# 2_waffling60-BAK_matrix.net
KiCad netlist of a schematic drawn in Altium Designer
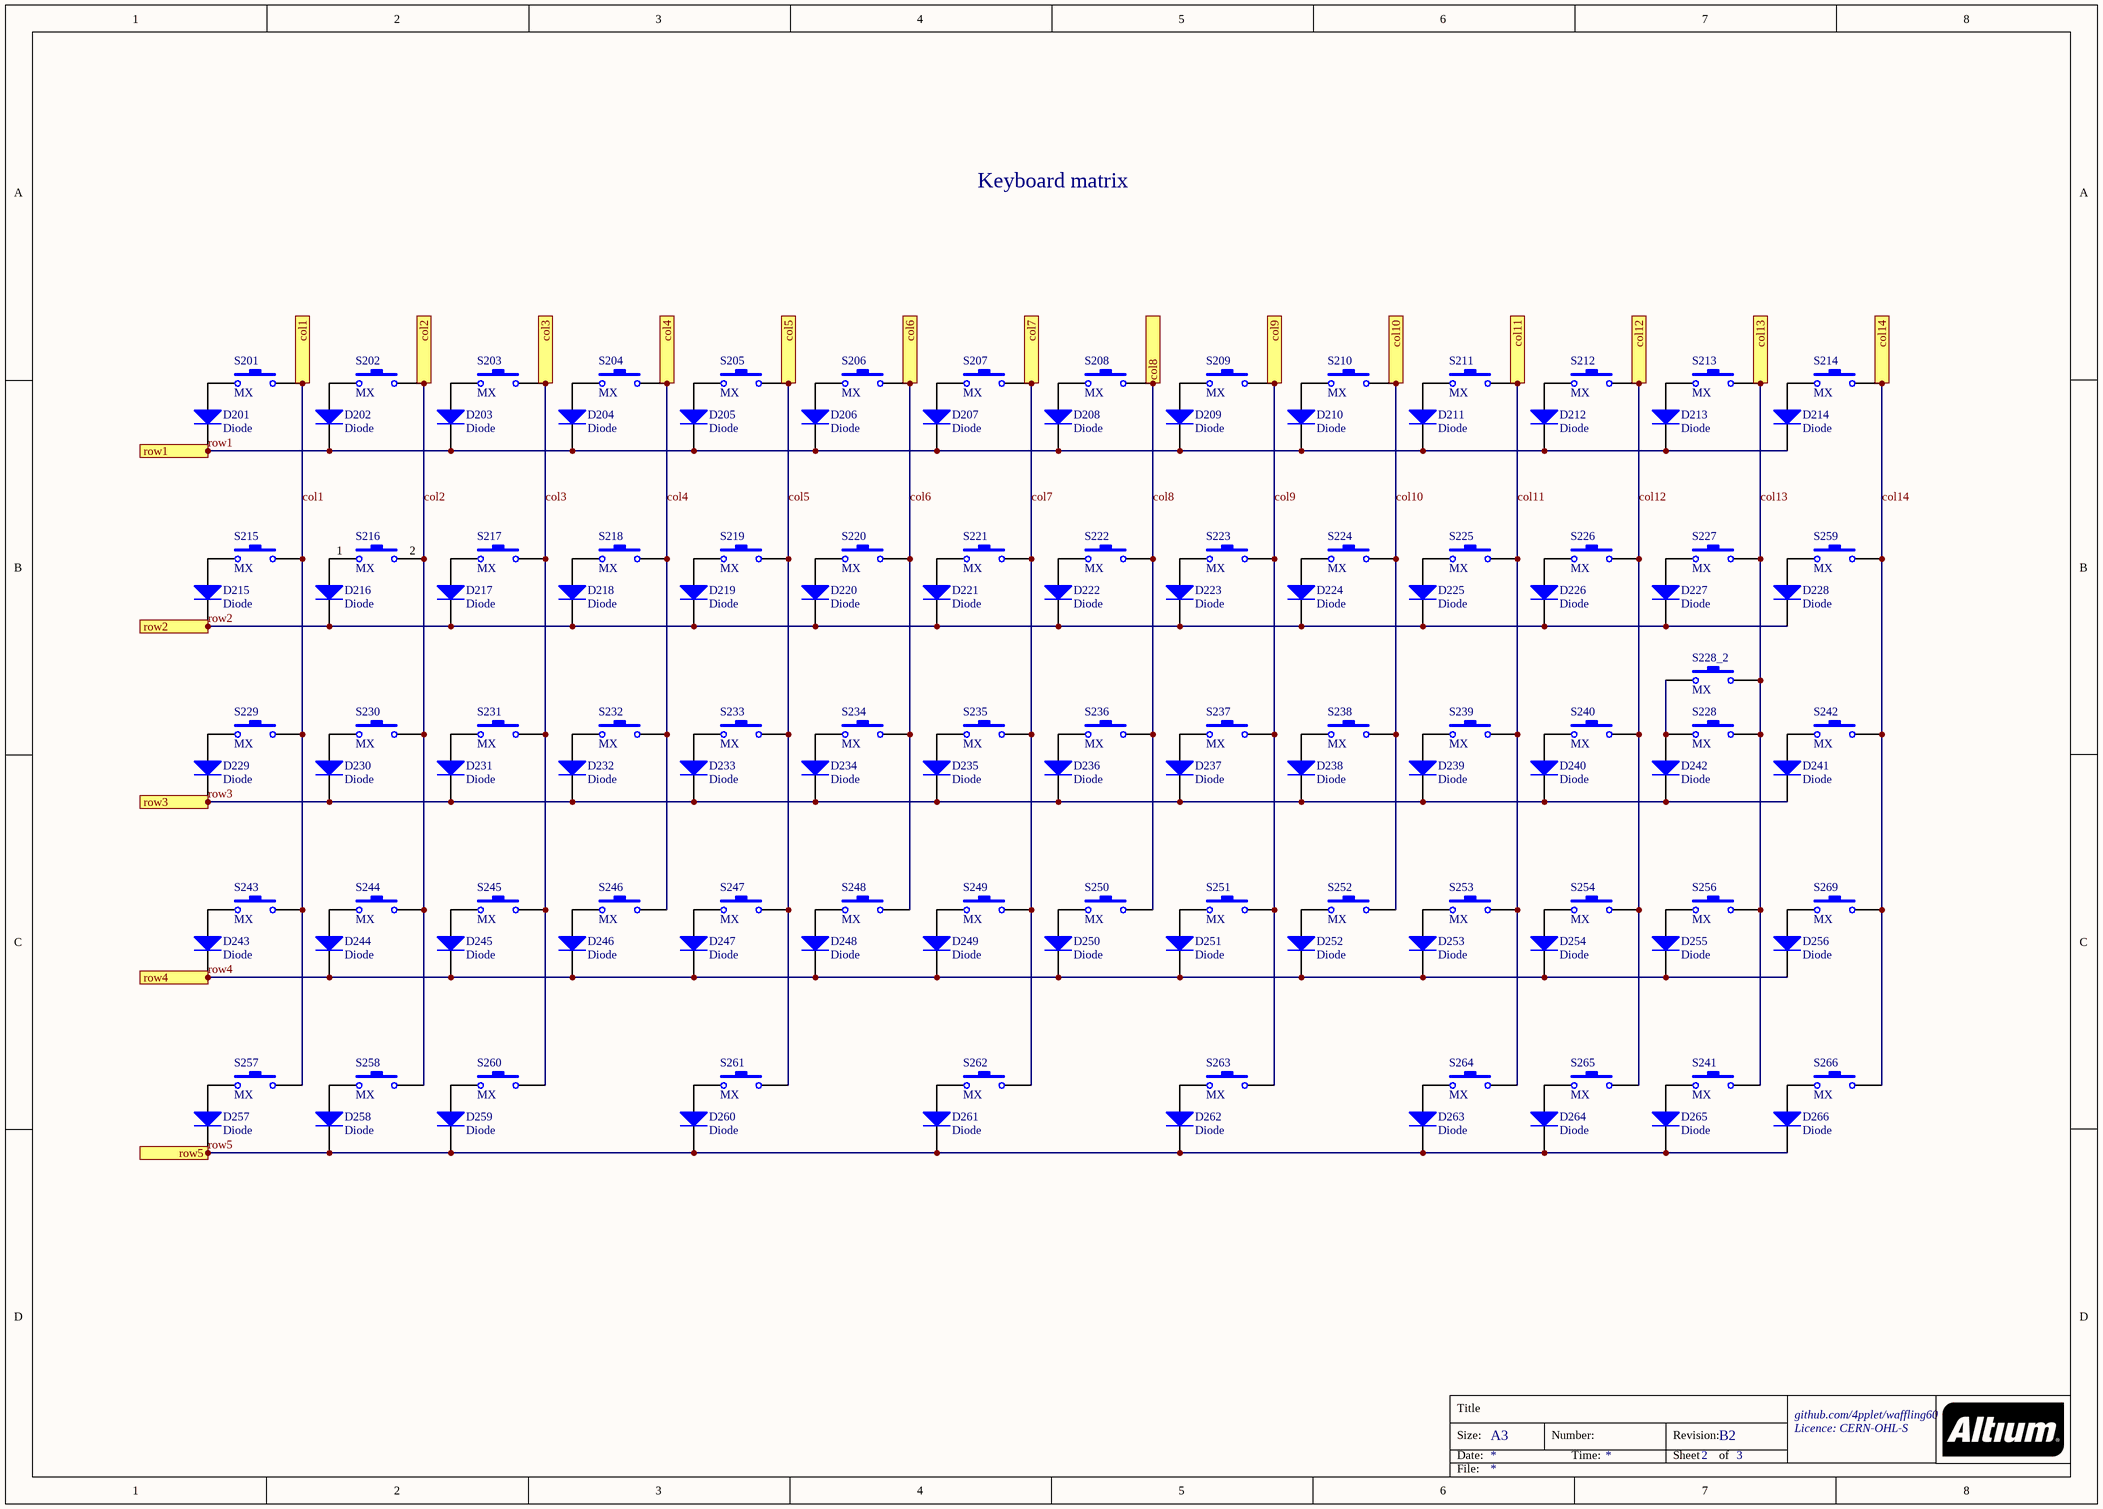
[diagram p0: 2_waffling60-BAK_matrix.SchDoc]

(export (version "E")
  (design (tool "Eeschema 10.0.6"))
  (components
    (comp (ref "D201")
      (value "Diode")
      (footprint "SOD-123")
      (description "Default Diode")
      (fields (field (name "LCSC PART #") "C81598") (field (name "MRF.PART") "1N4148W"))
      (libsource (lib "Miscellaneous Devices") (part "Diode"))
    )
    (comp (ref "D202")
      (value "Diode")
      (footprint "SOD-123")
      (description "Default Diode")
      (fields (field (name "LCSC PART #") "C81598") (field (name "MRF.PART") "1N4148W"))
      (libsource (lib "Miscellaneous Devices") (part "Diode"))
    )
    (comp (ref "D203")
      (value "Diode")
      (footprint "SOD-123")
      (description "Default Diode")
      (fields (field (name "LCSC PART #") "C81598") (field (name "MRF.PART") "1N4148W"))
      (libsource (lib "Miscellaneous Devices") (part "Diode"))
    )
    (comp (ref "D204")
      (value "Diode")
      (footprint "SOD-123")
      (description "Default Diode")
      (fields (field (name "LCSC PART #") "C81598") (field (name "MRF.PART") "1N4148W"))
      (libsource (lib "Miscellaneous Devices") (part "Diode"))
    )
    (comp (ref "D205")
      (value "Diode")
      (footprint "SOD-123")
      (description "Default Diode")
      (fields (field (name "LCSC PART #") "C81598") (field (name "MRF.PART") "1N4148W"))
      (libsource (lib "Miscellaneous Devices") (part "Diode"))
    )
    (comp (ref "D206")
      (value "Diode")
      (footprint "SOD-123")
      (description "Default Diode")
      (fields (field (name "LCSC PART #") "C81598") (field (name "MRF.PART") "1N4148W"))
      (libsource (lib "Miscellaneous Devices") (part "Diode"))
    )
    (comp (ref "D207")
      (value "Diode")
      (footprint "SOD-123")
      (description "Default Diode")
      (fields (field (name "LCSC PART #") "C81598") (field (name "MRF.PART") "1N4148W"))
      (libsource (lib "Miscellaneous Devices") (part "Diode"))
    )
    (comp (ref "D208")
      (value "Diode")
      (footprint "SOD-123")
      (description "Default Diode")
      (fields (field (name "LCSC PART #") "C81598") (field (name "MRF.PART") "1N4148W"))
      (libsource (lib "Miscellaneous Devices") (part "Diode"))
    )
    (comp (ref "D209")
      (value "Diode")
      (footprint "SOD-123")
      (description "Default Diode")
      (fields (field (name "LCSC PART #") "C81598") (field (name "MRF.PART") "1N4148W"))
      (libsource (lib "Miscellaneous Devices") (part "Diode"))
    )
    (comp (ref "D210")
      (value "Diode")
      (footprint "SOD-123")
      (description "Default Diode")
      (fields (field (name "LCSC PART #") "C81598") (field (name "MRF.PART") "1N4148W"))
      (libsource (lib "Miscellaneous Devices") (part "Diode"))
    )
    (comp (ref "D211")
      (value "Diode")
      (footprint "SOD-123")
      (description "Default Diode")
      (fields (field (name "LCSC PART #") "C81598") (field (name "MRF.PART") "1N4148W"))
      (libsource (lib "Miscellaneous Devices") (part "Diode"))
    )
    (comp (ref "D212")
      (value "Diode")
      (footprint "SOD-123")
      (description "Default Diode")
      (fields (field (name "LCSC PART #") "C81598") (field (name "MRF.PART") "1N4148W"))
      (libsource (lib "Miscellaneous Devices") (part "Diode"))
    )
    (comp (ref "D213")
      (value "Diode")
      (footprint "SOD-123")
      (description "Default Diode")
      (fields (field (name "LCSC PART #") "C81598") (field (name "MRF.PART") "1N4148W"))
      (libsource (lib "Miscellaneous Devices") (part "Diode"))
    )
    (comp (ref "D214")
      (value "Diode")
      (footprint "SOD-123")
      (description "Default Diode")
      (fields (field (name "LCSC PART #") "C81598") (field (name "MRF.PART") "1N4148W"))
      (libsource (lib "Miscellaneous Devices") (part "Diode"))
    )
    (comp (ref "D215")
      (value "Diode")
      (footprint "SOD-123")
      (description "Default Diode")
      (fields (field (name "LCSC PART #") "C81598") (field (name "MRF.PART") "1N4148W"))
      (libsource (lib "Miscellaneous Devices") (part "Diode"))
    )
    (comp (ref "D216")
      (value "Diode")
      (footprint "SOD-123")
      (description "Default Diode")
      (fields (field (name "LCSC PART #") "C81598") (field (name "MRF.PART") "1N4148W"))
      (libsource (lib "Miscellaneous Devices") (part "Diode"))
    )
    (comp (ref "D217")
      (value "Diode")
      (footprint "SOD-123")
      (description "Default Diode")
      (fields (field (name "LCSC PART #") "C81598") (field (name "MRF.PART") "1N4148W"))
      (libsource (lib "Miscellaneous Devices") (part "Diode"))
    )
    (comp (ref "D218")
      (value "Diode")
      (footprint "SOD-123")
      (description "Default Diode")
      (fields (field (name "LCSC PART #") "C81598") (field (name "MRF.PART") "1N4148W"))
      (libsource (lib "Miscellaneous Devices") (part "Diode"))
    )
    (comp (ref "D219")
      (value "Diode")
      (footprint "SOD-123")
      (description "Default Diode")
      (fields (field (name "LCSC PART #") "C81598") (field (name "MRF.PART") "1N4148W"))
      (libsource (lib "Miscellaneous Devices") (part "Diode"))
    )
    (comp (ref "D220")
      (value "Diode")
      (footprint "SOD-123")
      (description "Default Diode")
      (fields (field (name "LCSC PART #") "C81598") (field (name "MRF.PART") "1N4148W"))
      (libsource (lib "Miscellaneous Devices") (part "Diode"))
    )
    (comp (ref "D221")
      (value "Diode")
      (footprint "SOD-123")
      (description "Default Diode")
      (fields (field (name "LCSC PART #") "C81598") (field (name "MRF.PART") "1N4148W"))
      (libsource (lib "Miscellaneous Devices") (part "Diode"))
    )
    (comp (ref "D222")
      (value "Diode")
      (footprint "SOD-123")
      (description "Default Diode")
      (fields (field (name "LCSC PART #") "C81598") (field (name "MRF.PART") "1N4148W"))
      (libsource (lib "Miscellaneous Devices") (part "Diode"))
    )
    (comp (ref "D223")
      (value "Diode")
      (footprint "SOD-123")
      (description "Default Diode")
      (fields (field (name "LCSC PART #") "C81598") (field (name "MRF.PART") "1N4148W"))
      (libsource (lib "Miscellaneous Devices") (part "Diode"))
    )
    (comp (ref "D224")
      (value "Diode")
      (footprint "SOD-123")
      (description "Default Diode")
      (fields (field (name "LCSC PART #") "C81598") (field (name "MRF.PART") "1N4148W"))
      (libsource (lib "Miscellaneous Devices") (part "Diode"))
    )
    (comp (ref "D225")
      (value "Diode")
      (footprint "SOD-123")
      (description "Default Diode")
      (fields (field (name "LCSC PART #") "C81598") (field (name "MRF.PART") "1N4148W"))
      (libsource (lib "Miscellaneous Devices") (part "Diode"))
    )
    (comp (ref "D226")
      (value "Diode")
      (footprint "SOD-123")
      (description "Default Diode")
      (fields (field (name "LCSC PART #") "C81598") (field (name "MRF.PART") "1N4148W"))
      (libsource (lib "Miscellaneous Devices") (part "Diode"))
    )
    (comp (ref "D227")
      (value "Diode")
      (footprint "SOD-123")
      (description "Default Diode")
      (fields (field (name "LCSC PART #") "C81598") (field (name "MRF.PART") "1N4148W"))
      (libsource (lib "Miscellaneous Devices") (part "Diode"))
    )
    (comp (ref "D228")
      (value "Diode")
      (footprint "SOD-123")
      (description "Default Diode")
      (fields (field (name "LCSC PART #") "C81598") (field (name "MRF.PART") "1N4148W"))
      (libsource (lib "Miscellaneous Devices") (part "Diode"))
    )
    (comp (ref "D229")
      (value "Diode")
      (footprint "SOD-123")
      (description "Default Diode")
      (fields (field (name "LCSC PART #") "C81598") (field (name "MRF.PART") "1N4148W"))
      (libsource (lib "Miscellaneous Devices") (part "Diode"))
    )
    (comp (ref "D230")
      (value "Diode")
      (footprint "SOD-123")
      (description "Default Diode")
      (fields (field (name "LCSC PART #") "C81598") (field (name "MRF.PART") "1N4148W"))
      (libsource (lib "Miscellaneous Devices") (part "Diode"))
    )
    (comp (ref "D231")
      (value "Diode")
      (footprint "SOD-123")
      (description "Default Diode")
      (fields (field (name "LCSC PART #") "C81598") (field (name "MRF.PART") "1N4148W"))
      (libsource (lib "Miscellaneous Devices") (part "Diode"))
    )
    (comp (ref "D232")
      (value "Diode")
      (footprint "SOD-123")
      (description "Default Diode")
      (fields (field (name "LCSC PART #") "C81598") (field (name "MRF.PART") "1N4148W"))
      (libsource (lib "Miscellaneous Devices") (part "Diode"))
    )
    (comp (ref "D233")
      (value "Diode")
      (footprint "SOD-123")
      (description "Default Diode")
      (fields (field (name "LCSC PART #") "C81598") (field (name "MRF.PART") "1N4148W"))
      (libsource (lib "Miscellaneous Devices") (part "Diode"))
    )
    (comp (ref "D234")
      (value "Diode")
      (footprint "SOD-123")
      (description "Default Diode")
      (fields (field (name "LCSC PART #") "C81598") (field (name "MRF.PART") "1N4148W"))
      (libsource (lib "Miscellaneous Devices") (part "Diode"))
    )
    (comp (ref "D235")
      (value "Diode")
      (footprint "SOD-123")
      (description "Default Diode")
      (fields (field (name "LCSC PART #") "C81598") (field (name "MRF.PART") "1N4148W"))
      (libsource (lib "Miscellaneous Devices") (part "Diode"))
    )
    (comp (ref "D236")
      (value "Diode")
      (footprint "SOD-123")
      (description "Default Diode")
      (fields (field (name "LCSC PART #") "C81598") (field (name "MRF.PART") "1N4148W"))
      (libsource (lib "Miscellaneous Devices") (part "Diode"))
    )
    (comp (ref "D237")
      (value "Diode")
      (footprint "SOD-123")
      (description "Default Diode")
      (fields (field (name "LCSC PART #") "C81598") (field (name "MRF.PART") "1N4148W"))
      (libsource (lib "Miscellaneous Devices") (part "Diode"))
    )
    (comp (ref "D238")
      (value "Diode")
      (footprint "SOD-123")
      (description "Default Diode")
      (fields (field (name "LCSC PART #") "C81598") (field (name "MRF.PART") "1N4148W"))
      (libsource (lib "Miscellaneous Devices") (part "Diode"))
    )
    (comp (ref "D239")
      (value "Diode")
      (footprint "SOD-123")
      (description "Default Diode")
      (fields (field (name "LCSC PART #") "C81598") (field (name "MRF.PART") "1N4148W"))
      (libsource (lib "Miscellaneous Devices") (part "Diode"))
    )
    (comp (ref "D240")
      (value "Diode")
      (footprint "SOD-123")
      (description "Default Diode")
      (fields (field (name "LCSC PART #") "C81598") (field (name "MRF.PART") "1N4148W"))
      (libsource (lib "Miscellaneous Devices") (part "Diode"))
    )
    (comp (ref "D241")
      (value "Diode")
      (footprint "SOD-123")
      (description "Default Diode")
      (fields (field (name "LCSC PART #") "C81598") (field (name "MRF.PART") "1N4148W"))
      (libsource (lib "Miscellaneous Devices") (part "Diode"))
    )
    (comp (ref "D242")
      (value "Diode")
      (footprint "SOD-123")
      (description "Default Diode")
      (fields (field (name "LCSC PART #") "C81598") (field (name "MRF.PART") "1N4148W"))
      (libsource (lib "Miscellaneous Devices") (part "Diode"))
    )
    (comp (ref "D243")
      (value "Diode")
      (footprint "SOD-123")
      (description "Default Diode")
      (fields (field (name "LCSC PART #") "C81598") (field (name "MRF.PART") "1N4148W"))
      (libsource (lib "Miscellaneous Devices") (part "Diode"))
    )
    (comp (ref "D244")
      (value "Diode")
      (footprint "SOD-123")
      (description "Default Diode")
      (fields (field (name "LCSC PART #") "C81598") (field (name "MRF.PART") "1N4148W"))
      (libsource (lib "Miscellaneous Devices") (part "Diode"))
    )
    (comp (ref "D245")
      (value "Diode")
      (footprint "SOD-123")
      (description "Default Diode")
      (fields (field (name "LCSC PART #") "C81598") (field (name "MRF.PART") "1N4148W"))
      (libsource (lib "Miscellaneous Devices") (part "Diode"))
    )
    (comp (ref "D246")
      (value "Diode")
      (footprint "SOD-123")
      (description "Default Diode")
      (fields (field (name "LCSC PART #") "C81598") (field (name "MRF.PART") "1N4148W"))
      (libsource (lib "Miscellaneous Devices") (part "Diode"))
    )
    (comp (ref "D247")
      (value "Diode")
      (footprint "SOD-123")
      (description "Default Diode")
      (fields (field (name "LCSC PART #") "C81598") (field (name "MRF.PART") "1N4148W"))
      (libsource (lib "Miscellaneous Devices") (part "Diode"))
    )
    (comp (ref "D248")
      (value "Diode")
      (footprint "SOD-123")
      (description "Default Diode")
      (fields (field (name "LCSC PART #") "C81598") (field (name "MRF.PART") "1N4148W"))
      (libsource (lib "Miscellaneous Devices") (part "Diode"))
    )
    (comp (ref "D249")
      (value "Diode")
      (footprint "SOD-123")
      (description "Default Diode")
      (fields (field (name "LCSC PART #") "C81598") (field (name "MRF.PART") "1N4148W"))
      (libsource (lib "Miscellaneous Devices") (part "Diode"))
    )
    (comp (ref "D250")
      (value "Diode")
      (footprint "SOD-123")
      (description "Default Diode")
      (fields (field (name "LCSC PART #") "C81598") (field (name "MRF.PART") "1N4148W"))
      (libsource (lib "Miscellaneous Devices") (part "Diode"))
    )
    (comp (ref "D251")
      (value "Diode")
      (footprint "SOD-123")
      (description "Default Diode")
      (fields (field (name "LCSC PART #") "C81598") (field (name "MRF.PART") "1N4148W"))
      (libsource (lib "Miscellaneous Devices") (part "Diode"))
    )
    (comp (ref "D252")
      (value "Diode")
      (footprint "SOD-123")
      (description "Default Diode")
      (fields (field (name "LCSC PART #") "C81598") (field (name "MRF.PART") "1N4148W"))
      (libsource (lib "Miscellaneous Devices") (part "Diode"))
    )
    (comp (ref "D253")
      (value "Diode")
      (footprint "SOD-123")
      (description "Default Diode")
      (fields (field (name "LCSC PART #") "C81598") (field (name "MRF.PART") "1N4148W"))
      (libsource (lib "Miscellaneous Devices") (part "Diode"))
    )
    (comp (ref "D254")
      (value "Diode")
      (footprint "SOD-123")
      (description "Default Diode")
      (fields (field (name "LCSC PART #") "C81598") (field (name "MRF.PART") "1N4148W"))
      (libsource (lib "Miscellaneous Devices") (part "Diode"))
    )
    (comp (ref "D255")
      (value "Diode")
      (footprint "SOD-123")
      (description "Default Diode")
      (fields (field (name "LCSC PART #") "C81598") (field (name "MRF.PART") "1N4148W"))
      (libsource (lib "Miscellaneous Devices") (part "Diode"))
    )
    (comp (ref "D256")
      (value "Diode")
      (footprint "SOD-123")
      (description "Default Diode")
      (fields (field (name "LCSC PART #") "C81598") (field (name "MRF.PART") "1N4148W"))
      (libsource (lib "Miscellaneous Devices") (part "Diode"))
    )
    (comp (ref "D257")
      (value "Diode")
      (footprint "SOD-123")
      (description "Default Diode")
      (fields (field (name "LCSC PART #") "C81598") (field (name "MRF.PART") "1N4148W"))
      (libsource (lib "Miscellaneous Devices") (part "Diode"))
    )
    (comp (ref "D258")
      (value "Diode")
      (footprint "SOD-123")
      (description "Default Diode")
      (fields (field (name "LCSC PART #") "C81598") (field (name "MRF.PART") "1N4148W"))
      (libsource (lib "Miscellaneous Devices") (part "Diode"))
    )
    (comp (ref "D259")
      (value "Diode")
      (footprint "SOD-123")
      (description "Default Diode")
      (fields (field (name "LCSC PART #") "C81598") (field (name "MRF.PART") "1N4148W"))
      (libsource (lib "Miscellaneous Devices") (part "Diode"))
    )
    (comp (ref "D260")
      (value "Diode")
      (footprint "SOD-123")
      (description "Default Diode")
      (fields (field (name "LCSC PART #") "C81598") (field (name "MRF.PART") "1N4148W"))
      (libsource (lib "Miscellaneous Devices") (part "Diode"))
    )
    (comp (ref "D261")
      (value "Diode")
      (footprint "SOD-123")
      (description "Default Diode")
      (fields (field (name "LCSC PART #") "C81598") (field (name "MRF.PART") "1N4148W"))
      (libsource (lib "Miscellaneous Devices") (part "Diode"))
    )
    (comp (ref "D262")
      (value "Diode")
      (footprint "SOD-123")
      (description "Default Diode")
      (fields (field (name "LCSC PART #") "C81598") (field (name "MRF.PART") "1N4148W"))
      (libsource (lib "Miscellaneous Devices") (part "Diode"))
    )
    (comp (ref "D263")
      (value "Diode")
      (footprint "SOD-123")
      (description "Default Diode")
      (fields (field (name "LCSC PART #") "C81598") (field (name "MRF.PART") "1N4148W"))
      (libsource (lib "Miscellaneous Devices") (part "Diode"))
    )
    (comp (ref "D264")
      (value "Diode")
      (footprint "SOD-123")
      (description "Default Diode")
      (fields (field (name "LCSC PART #") "C81598") (field (name "MRF.PART") "1N4148W"))
      (libsource (lib "Miscellaneous Devices") (part "Diode"))
    )
    (comp (ref "D265")
      (value "Diode")
      (footprint "SOD-123")
      (description "Default Diode")
      (fields (field (name "LCSC PART #") "C81598") (field (name "MRF.PART") "1N4148W"))
      (libsource (lib "Miscellaneous Devices") (part "Diode"))
    )
    (comp (ref "D266")
      (value "Diode")
      (footprint "SOD-123")
      (description "Default Diode")
      (fields (field (name "LCSC PART #") "C81598") (field (name "MRF.PART") "1N4148W"))
      (libsource (lib "Miscellaneous Devices") (part "Diode"))
    )
    (comp (ref "S201")
      (value "MX")
      (footprint "MX-switch - switched pol")
      (description "Switch")
      (libsource (lib "Miscellaneous Devices") (part "SW-PB"))
    )
    (comp (ref "S202")
      (value "MX")
      (footprint "MX-switch")
      (description "Switch")
      (libsource (lib "Miscellaneous Devices") (part "SW-PB"))
    )
    (comp (ref "S203")
      (value "MX")
      (footprint "MX-switch - switched pol")
      (description "Switch")
      (libsource (lib "Miscellaneous Devices") (part "SW-PB"))
    )
    (comp (ref "S204")
      (value "MX")
      (footprint "MX-switch - switched pol")
      (description "Switch")
      (libsource (lib "Miscellaneous Devices") (part "SW-PB"))
    )
    (comp (ref "S205")
      (value "MX")
      (footprint "MX-switch - switched pol")
      (description "Switch")
      (libsource (lib "Miscellaneous Devices") (part "SW-PB"))
    )
    (comp (ref "S206")
      (value "MX")
      (footprint "MX-switch - switched pol")
      (description "Switch")
      (libsource (lib "Miscellaneous Devices") (part "SW-PB"))
    )
    (comp (ref "S207")
      (value "MX")
      (footprint "MX-switch - switched pol")
      (description "Switch")
      (libsource (lib "Miscellaneous Devices") (part "SW-PB"))
    )
    (comp (ref "S208")
      (value "MX")
      (footprint "MX-switch - switched pol")
      (description "Switch")
      (libsource (lib "Miscellaneous Devices") (part "SW-PB"))
    )
    (comp (ref "S209")
      (value "MX")
      (footprint "MX-switch - switched pol")
      (description "Switch")
      (libsource (lib "Miscellaneous Devices") (part "SW-PB"))
    )
    (comp (ref "S210")
      (value "MX")
      (footprint "MX-switch - switched pol")
      (description "Switch")
      (libsource (lib "Miscellaneous Devices") (part "SW-PB"))
    )
    (comp (ref "S211")
      (value "MX")
      (footprint "MX-switch - switched pol")
      (description "Switch")
      (libsource (lib "Miscellaneous Devices") (part "SW-PB"))
    )
    (comp (ref "S212")
      (value "MX")
      (footprint "MX-switch - switched pol")
      (description "Switch")
      (libsource (lib "Miscellaneous Devices") (part "SW-PB"))
    )
    (comp (ref "S213")
      (value "MX")
      (footprint "MX-switch - switched pol")
      (description "Switch")
      (libsource (lib "Miscellaneous Devices") (part "SW-PB"))
    )
    (comp (ref "S214")
      (value "MX")
      (footprint "MX-switch")
      (description "Switch")
      (libsource (lib "Miscellaneous Devices") (part "SW-PB"))
    )
    (comp (ref "S215")
      (value "MX")
      (footprint "MX-switch")
      (description "TAB")
      (libsource (lib "Miscellaneous Devices") (part "SW-PB"))
    )
    (comp (ref "S216")
      (value "MX")
      (footprint "MX-switch")
      (description "Switch")
      (libsource (lib "") (part "SW-PB_1"))
    )
    (comp (ref "S217")
      (value "MX")
      (footprint "MX-switch - switched pol")
      (description "Switch")
      (libsource (lib "Miscellaneous Devices") (part "SW-PB"))
    )
    (comp (ref "S218")
      (value "MX")
      (footprint "MX-switch - switched pol")
      (description "Switch")
      (libsource (lib "Miscellaneous Devices") (part "SW-PB"))
    )
    (comp (ref "S219")
      (value "MX")
      (footprint "MX-switch - switched pol")
      (description "Switch")
      (libsource (lib "Miscellaneous Devices") (part "SW-PB"))
    )
    (comp (ref "S220")
      (value "MX")
      (footprint "MX-switch")
      (description "Switch")
      (libsource (lib "Miscellaneous Devices") (part "SW-PB"))
    )
    (comp (ref "S221")
      (value "MX")
      (footprint "MX-switch - switched pol")
      (description "Switch")
      (libsource (lib "Miscellaneous Devices") (part "SW-PB"))
    )
    (comp (ref "S222")
      (value "MX")
      (footprint "MX-switch")
      (description "Switch")
      (libsource (lib "Miscellaneous Devices") (part "SW-PB"))
    )
    (comp (ref "S223")
      (value "MX")
      (footprint "MX-switch - switched pol")
      (description "Switch")
      (libsource (lib "Miscellaneous Devices") (part "SW-PB"))
    )
    (comp (ref "S224")
      (value "MX")
      (footprint "MX-switch - switched pol")
      (description "Switch")
      (libsource (lib "Miscellaneous Devices") (part "SW-PB"))
    )
    (comp (ref "S225")
      (value "MX")
      (footprint "MX-switch - switched pol")
      (description "Switch")
      (libsource (lib "Miscellaneous Devices") (part "SW-PB"))
    )
    (comp (ref "S226")
      (value "MX")
      (footprint "MX-switch")
      (description "Switch")
      (libsource (lib "Miscellaneous Devices") (part "SW-PB"))
    )
    (comp (ref "S227")
      (value "MX")
      (footprint "MX-switch")
      (description "Switch")
      (libsource (lib "Miscellaneous Devices") (part "SW-PB"))
    )
    (comp (ref "S228")
      (value "MX")
      (footprint "MX-switch - 1.5U - switched pol")
      (description "Switch")
      (libsource (lib "Miscellaneous Devices") (part "SW-PB"))
    )
    (comp (ref "S228_2")
      (value "MX")
      (footprint "MX-switch - switched pol")
      (description "Switch")
      (libsource (lib "Miscellaneous Devices") (part "SW-PB"))
    )
    (comp (ref "S229")
      (value "MX")
      (footprint "MX-switch - CAPS")
      (description "Switch")
      (libsource (lib "Miscellaneous Devices") (part "SW-PB"))
    )
    (comp (ref "S230")
      (value "MX")
      (footprint "MX-switch")
      (description "Switch")
      (libsource (lib "Miscellaneous Devices") (part "SW-PB"))
    )
    (comp (ref "S231")
      (value "MX")
      (footprint "MX-switch - switched pol")
      (description "Switch")
      (libsource (lib "Miscellaneous Devices") (part "SW-PB"))
    )
    (comp (ref "S232")
      (value "MX")
      (footprint "MX-switch - switched pol")
      (description "Switch")
      (libsource (lib "Miscellaneous Devices") (part "SW-PB"))
    )
    (comp (ref "S233")
      (value "MX")
      (footprint "MX-switch - switched pol")
      (description "Switch")
      (libsource (lib "Miscellaneous Devices") (part "SW-PB"))
    )
    (comp (ref "S234")
      (value "MX")
      (footprint "MX-switch - switched pol")
      (description "Switch")
      (libsource (lib "Miscellaneous Devices") (part "SW-PB"))
    )
    (comp (ref "S235")
      (value "MX")
      (footprint "MX-switch - switched pol")
      (description "Switch")
      (libsource (lib "Miscellaneous Devices") (part "SW-PB"))
    )
    (comp (ref "S236")
      (value "MX")
      (footprint "MX-switch - switched pol")
      (description "Switch")
      (libsource (lib "Miscellaneous Devices") (part "SW-PB"))
    )
    (comp (ref "S237")
      (value "MX")
      (footprint "MX-switch - switched pol")
      (description "Switch")
      (libsource (lib "Miscellaneous Devices") (part "SW-PB"))
    )
    (comp (ref "S238")
      (value "MX")
      (footprint "MX-switch - switched pol")
      (description "Switch")
      (libsource (lib "Miscellaneous Devices") (part "SW-PB"))
    )
    (comp (ref "S239")
      (value "MX")
      (footprint "MX-switch - switched pol")
      (description "Switch")
      (libsource (lib "Miscellaneous Devices") (part "SW-PB"))
    )
    (comp (ref "S240")
      (value "MX")
      (footprint "MX-switch - switched pol")
      (description "Switch")
      (libsource (lib "Miscellaneous Devices") (part "SW-PB"))
    )
    (comp (ref "S241")
      (value "MX")
      (footprint "MX-switch - 1u MOD-R")
      (description "Switch")
      (libsource (lib "Miscellaneous Devices") (part "SW-PB"))
    )
    (comp (ref "S242")
      (value "MX")
      (footprint "MX-switch - Enter")
      (description "Switch")
      (libsource (lib "Miscellaneous Devices") (part "SW-PB"))
    )
    (comp (ref "S243")
      (value "MX")
      (footprint "MX-switch - Left shift")
      (description "Switch")
      (libsource (lib "Miscellaneous Devices") (part "SW-PB"))
    )
    (comp (ref "S244")
      (value "MX")
      (footprint "MX-switch")
      (description "Switch")
      (libsource (lib "Miscellaneous Devices") (part "SW-PB"))
    )
    (comp (ref "S245")
      (value "MX")
      (footprint "MX-switch - switched pol")
      (description "Switch")
      (libsource (lib "Miscellaneous Devices") (part "SW-PB"))
    )
    (comp (ref "S246")
      (value "MX")
      (footprint "MX-switch - switched pol")
      (description "Switch")
      (libsource (lib "Miscellaneous Devices") (part "SW-PB"))
    )
    (comp (ref "S247")
      (value "MX")
      (footprint "MX-switch - switched pol")
      (description "Switch")
      (libsource (lib "Miscellaneous Devices") (part "SW-PB"))
    )
    (comp (ref "S248")
      (value "MX")
      (footprint "MX-switch - switched pol")
      (description "Switch")
      (libsource (lib "Miscellaneous Devices") (part "SW-PB"))
    )
    (comp (ref "S249")
      (value "MX")
      (footprint "MX-switch - switched pol")
      (description "Switch")
      (libsource (lib "Miscellaneous Devices") (part "SW-PB"))
    )
    (comp (ref "S250")
      (value "MX")
      (footprint "MX-switch - switched pol")
      (description "Switch")
      (libsource (lib "Miscellaneous Devices") (part "SW-PB"))
    )
    (comp (ref "S251")
      (value "MX")
      (footprint "MX-switch - switched pol")
      (description "Switch")
      (libsource (lib "Miscellaneous Devices") (part "SW-PB"))
    )
    (comp (ref "S252")
      (value "MX")
      (footprint "MX-switch - switched pol")
      (description "Switch")
      (libsource (lib "Miscellaneous Devices") (part "SW-PB"))
    )
    (comp (ref "S253")
      (value "MX")
      (footprint "MX-switch - switched pol")
      (description "Switch")
      (libsource (lib "Miscellaneous Devices") (part "SW-PB"))
    )
    (comp (ref "S254")
      (value "MX")
      (footprint "MX-switch - switched pol")
      (description "Switch")
      (libsource (lib "Miscellaneous Devices") (part "SW-PB"))
    )
    (comp (ref "S256")
      (value "MX")
      (footprint "MX-switch - right shift")
      (description "Switch")
      (libsource (lib "Miscellaneous Devices") (part "SW-PB"))
    )
    (comp (ref "S257")
      (value "MX")
      (footprint "MX-switch - 1.5u MOD-L")
      (description "Switch")
      (libsource (lib "Miscellaneous Devices") (part "SW-PB"))
    )
    (comp (ref "S258")
      (value "MX")
      (footprint "MX-switch - 1u MOD-L")
      (description "Switch")
      (libsource (lib "Miscellaneous Devices") (part "SW-PB"))
    )
    (comp (ref "S259")
      (value "MX")
      (footprint "MX-switch - backspace")
      (description "Switch")
      (libsource (lib "Miscellaneous Devices") (part "SW-PB"))
    )
    (comp (ref "S260")
      (value "MX")
      (footprint "MX-switch - 1.5u MOD-L")
      (description "Switch")
      (libsource (lib "Miscellaneous Devices") (part "SW-PB"))
    )
    (comp (ref "S261")
      (value "MX")
      (footprint "MX-SWITCH - L SPLIT SPACE_V2")
      (description "Switch")
      (libsource (lib "Miscellaneous Devices") (part "SW-PB"))
    )
    (comp (ref "S262")
      (value "MX")
      (footprint "MX-switch - Space_V3")
      (description "Switch")
      (libsource (lib "Miscellaneous Devices") (part "SW-PB"))
    )
    (comp (ref "S263")
      (value "MX")
      (footprint "MX-SWITCH - R SPLIT SPACE_V2")
      (description "Switch")
      (libsource (lib "Miscellaneous Devices") (part "SW-PB"))
    )
    (comp (ref "S264")
      (value "MX")
      (footprint "MX-switch - switched pol")
      (description "Switch")
      (libsource (lib "Miscellaneous Devices") (part "SW-PB"))
    )
    (comp (ref "S265")
      (value "MX")
      (footprint "MX-switch - 1.5u MOD-R")
      (description "Switch")
      (libsource (lib "Miscellaneous Devices") (part "SW-PB"))
    )
    (comp (ref "S266")
      (value "MX")
      (footprint "MX-switch - 1.5u MOD-R")
      (description "Switch")
      (libsource (lib "Miscellaneous Devices") (part "SW-PB"))
    )
    (comp (ref "S269")
      (value "MX")
      (footprint "MX-switch")
      (description "Switch")
      (libsource (lib "Miscellaneous Devices") (part "SW-PB"))
    )
  )
  (nets
    (net (code "1") (name "/col1") (class "Default")
      (node (ref "S201") (pin "2") (pinfunction "2_2") (pintype "passive"))
      (node (ref "S215") (pin "2") (pinfunction "2_2") (pintype "passive"))
      (node (ref "S229") (pin "2") (pinfunction "2_2") (pintype "passive"))
      (node (ref "S243") (pin "2") (pinfunction "2_2") (pintype "passive"))
      (node (ref "S257") (pin "1") (pinfunction "1_1") (pintype "passive"))
    )
    (net (code "2") (name "/col2") (class "Default")
      (node (ref "S202") (pin "2") (pinfunction "2_2") (pintype "passive"))
      (node (ref "S216") (pin "2") (pinfunction "2_2") (pintype "passive"))
      (node (ref "S230") (pin "2") (pinfunction "2_2") (pintype "passive"))
      (node (ref "S244") (pin "1") (pinfunction "1_1") (pintype "passive"))
      (node (ref "S258") (pin "1") (pinfunction "1_1") (pintype "passive"))
    )
    (net (code "3") (name "/col3") (class "Default")
      (node (ref "S203") (pin "2") (pinfunction "2_2") (pintype "passive"))
      (node (ref "S217") (pin "2") (pinfunction "2_2") (pintype "passive"))
      (node (ref "S231") (pin "2") (pinfunction "2_2") (pintype "passive"))
      (node (ref "S245") (pin "2") (pinfunction "2_2") (pintype "passive"))
      (node (ref "S260") (pin "1") (pinfunction "1_1") (pintype "passive"))
    )
    (net (code "4") (name "/col4") (class "Default")
      (node (ref "S204") (pin "2") (pinfunction "2_2") (pintype "passive"))
      (node (ref "S218") (pin "2") (pinfunction "2_2") (pintype "passive"))
      (node (ref "S232") (pin "2") (pinfunction "2_2") (pintype "passive"))
      (node (ref "S246") (pin "2") (pinfunction "2_2") (pintype "passive"))
    )
    (net (code "5") (name "/col5") (class "Default")
      (node (ref "S205") (pin "2") (pinfunction "2_2") (pintype "passive"))
      (node (ref "S219") (pin "2") (pinfunction "2_2") (pintype "passive"))
      (node (ref "S233") (pin "2") (pinfunction "2_2") (pintype "passive"))
      (node (ref "S247") (pin "2") (pinfunction "2_2") (pintype "passive"))
      (node (ref "S261") (pin "2") (pinfunction "2_2") (pintype "passive"))
    )
    (net (code "6") (name "/col6") (class "Default")
      (node (ref "S206") (pin "2") (pinfunction "2_2") (pintype "passive"))
      (node (ref "S220") (pin "2") (pinfunction "2_2") (pintype "passive"))
      (node (ref "S234") (pin "2") (pinfunction "2_2") (pintype "passive"))
      (node (ref "S248") (pin "2") (pinfunction "2_2") (pintype "passive"))
    )
    (net (code "7") (name "/col7") (class "Default")
      (node (ref "S207") (pin "2") (pinfunction "2_2") (pintype "passive"))
      (node (ref "S221") (pin "2") (pinfunction "2_2") (pintype "passive"))
      (node (ref "S235") (pin "2") (pinfunction "2_2") (pintype "passive"))
      (node (ref "S249") (pin "2") (pinfunction "2_2") (pintype "passive"))
      (node (ref "S262") (pin "1") (pinfunction "1_1") (pintype "passive"))
    )
    (net (code "8") (name "/col8") (class "Default")
      (node (ref "S208") (pin "2") (pinfunction "2_2") (pintype "passive"))
      (node (ref "S222") (pin "2") (pinfunction "2_2") (pintype "passive"))
      (node (ref "S236") (pin "2") (pinfunction "2_2") (pintype "passive"))
      (node (ref "S250") (pin "2") (pinfunction "2_2") (pintype "passive"))
    )
    (net (code "9") (name "/col9") (class "Default")
      (node (ref "S209") (pin "2") (pinfunction "2_2") (pintype "passive"))
      (node (ref "S223") (pin "2") (pinfunction "2_2") (pintype "passive"))
      (node (ref "S237") (pin "2") (pinfunction "2_2") (pintype "passive"))
      (node (ref "S251") (pin "2") (pinfunction "2_2") (pintype "passive"))
      (node (ref "S263") (pin "1") (pinfunction "1_1") (pintype "passive"))
    )
    (net (code "10") (name "/col10") (class "Default")
      (node (ref "S210") (pin "2") (pinfunction "2_2") (pintype "passive"))
      (node (ref "S224") (pin "2") (pinfunction "2_2") (pintype "passive"))
      (node (ref "S238") (pin "2") (pinfunction "2_2") (pintype "passive"))
      (node (ref "S252") (pin "2") (pinfunction "2_2") (pintype "passive"))
    )
    (net (code "11") (name "/col11") (class "Default")
      (node (ref "S211") (pin "2") (pinfunction "2_2") (pintype "passive"))
      (node (ref "S225") (pin "2") (pinfunction "2_2") (pintype "passive"))
      (node (ref "S239") (pin "2") (pinfunction "2_2") (pintype "passive"))
      (node (ref "S253") (pin "2") (pinfunction "2_2") (pintype "passive"))
      (node (ref "S264") (pin "2") (pinfunction "2_2") (pintype "passive"))
    )
    (net (code "12") (name "/col12") (class "Default")
      (node (ref "S212") (pin "2") (pinfunction "2_2") (pintype "passive"))
      (node (ref "S226") (pin "2") (pinfunction "2_2") (pintype "passive"))
      (node (ref "S240") (pin "2") (pinfunction "2_2") (pintype "passive"))
      (node (ref "S254") (pin "2") (pinfunction "2_2") (pintype "passive"))
      (node (ref "S265") (pin "2") (pinfunction "2_2") (pintype "passive"))
    )
    (net (code "13") (name "/col13") (class "Default")
      (node (ref "S213") (pin "2") (pinfunction "2_2") (pintype "passive"))
      (node (ref "S227") (pin "2") (pinfunction "2_2") (pintype "passive"))
      (node (ref "S228") (pin "2") (pinfunction "2_2") (pintype "passive"))
      (node (ref "S228_2") (pin "2") (pinfunction "2_2") (pintype "passive"))
      (node (ref "S241") (pin "2") (pinfunction "2_2") (pintype "passive"))
      (node (ref "S256") (pin "2") (pinfunction "2_2") (pintype "passive"))
    )
    (net (code "14") (name "/col14") (class "Default")
      (node (ref "S214") (pin "2") (pinfunction "2_2") (pintype "passive"))
      (node (ref "S242") (pin "2") (pinfunction "2_2") (pintype "passive"))
      (node (ref "S259") (pin "2") (pinfunction "2_2") (pintype "passive"))
      (node (ref "S266") (pin "2") (pinfunction "2_2") (pintype "passive"))
      (node (ref "S269") (pin "2") (pinfunction "2_2") (pintype "passive"))
    )
    (net (code "15") (name "/row1") (class "Default")
      (node (ref "D201") (pin "2") (pinfunction "K_2") (pintype "passive"))
      (node (ref "D202") (pin "2") (pinfunction "K_2") (pintype "passive"))
      (node (ref "D203") (pin "2") (pinfunction "K_2") (pintype "passive"))
      (node (ref "D204") (pin "2") (pinfunction "K_2") (pintype "passive"))
      (node (ref "D205") (pin "2") (pinfunction "K_2") (pintype "passive"))
      (node (ref "D206") (pin "2") (pinfunction "K_2") (pintype "passive"))
      (node (ref "D207") (pin "2") (pinfunction "K_2") (pintype "passive"))
      (node (ref "D208") (pin "2") (pinfunction "K_2") (pintype "passive"))
      (node (ref "D209") (pin "2") (pinfunction "K_2") (pintype "passive"))
      (node (ref "D210") (pin "2") (pinfunction "K_2") (pintype "passive"))
      (node (ref "D211") (pin "2") (pinfunction "K_2") (pintype "passive"))
      (node (ref "D212") (pin "2") (pinfunction "K_2") (pintype "passive"))
      (node (ref "D213") (pin "2") (pinfunction "K_2") (pintype "passive"))
      (node (ref "D214") (pin "2") (pinfunction "K_2") (pintype "passive"))
    )
    (net (code "16") (name "/row2") (class "Default")
      (node (ref "D215") (pin "2") (pinfunction "K_2") (pintype "passive"))
      (node (ref "D216") (pin "2") (pinfunction "K_2") (pintype "passive"))
      (node (ref "D217") (pin "2") (pinfunction "K_2") (pintype "passive"))
      (node (ref "D218") (pin "2") (pinfunction "K_2") (pintype "passive"))
      (node (ref "D219") (pin "2") (pinfunction "K_2") (pintype "passive"))
      (node (ref "D220") (pin "2") (pinfunction "K_2") (pintype "passive"))
      (node (ref "D221") (pin "2") (pinfunction "K_2") (pintype "passive"))
      (node (ref "D222") (pin "2") (pinfunction "K_2") (pintype "passive"))
      (node (ref "D223") (pin "2") (pinfunction "K_2") (pintype "passive"))
      (node (ref "D224") (pin "2") (pinfunction "K_2") (pintype "passive"))
      (node (ref "D225") (pin "2") (pinfunction "K_2") (pintype "passive"))
      (node (ref "D226") (pin "2") (pinfunction "K_2") (pintype "passive"))
      (node (ref "D227") (pin "2") (pinfunction "K_2") (pintype "passive"))
      (node (ref "D228") (pin "2") (pinfunction "K_2") (pintype "passive"))
    )
    (net (code "17") (name "/row3") (class "Default")
      (node (ref "D229") (pin "2") (pinfunction "K_2") (pintype "passive"))
      (node (ref "D230") (pin "2") (pinfunction "K_2") (pintype "passive"))
      (node (ref "D231") (pin "2") (pinfunction "K_2") (pintype "passive"))
      (node (ref "D232") (pin "2") (pinfunction "K_2") (pintype "passive"))
      (node (ref "D233") (pin "2") (pinfunction "K_2") (pintype "passive"))
      (node (ref "D234") (pin "2") (pinfunction "K_2") (pintype "passive"))
      (node (ref "D235") (pin "2") (pinfunction "K_2") (pintype "passive"))
      (node (ref "D236") (pin "2") (pinfunction "K_2") (pintype "passive"))
      (node (ref "D237") (pin "2") (pinfunction "K_2") (pintype "passive"))
      (node (ref "D238") (pin "2") (pinfunction "K_2") (pintype "passive"))
      (node (ref "D239") (pin "2") (pinfunction "K_2") (pintype "passive"))
      (node (ref "D240") (pin "2") (pinfunction "K_2") (pintype "passive"))
      (node (ref "D241") (pin "2") (pinfunction "K_2") (pintype "passive"))
      (node (ref "D242") (pin "2") (pinfunction "K_2") (pintype "passive"))
    )
    (net (code "18") (name "/row4") (class "Default")
      (node (ref "D243") (pin "2") (pinfunction "K_2") (pintype "passive"))
      (node (ref "D244") (pin "2") (pinfunction "K_2") (pintype "passive"))
      (node (ref "D245") (pin "2") (pinfunction "K_2") (pintype "passive"))
      (node (ref "D246") (pin "2") (pinfunction "K_2") (pintype "passive"))
      (node (ref "D247") (pin "2") (pinfunction "K_2") (pintype "passive"))
      (node (ref "D248") (pin "2") (pinfunction "K_2") (pintype "passive"))
      (node (ref "D249") (pin "2") (pinfunction "K_2") (pintype "passive"))
      (node (ref "D250") (pin "2") (pinfunction "K_2") (pintype "passive"))
      (node (ref "D251") (pin "2") (pinfunction "K_2") (pintype "passive"))
      (node (ref "D252") (pin "2") (pinfunction "K_2") (pintype "passive"))
      (node (ref "D253") (pin "2") (pinfunction "K_2") (pintype "passive"))
      (node (ref "D254") (pin "2") (pinfunction "K_2") (pintype "passive"))
      (node (ref "D255") (pin "2") (pinfunction "K_2") (pintype "passive"))
      (node (ref "D256") (pin "2") (pinfunction "K_2") (pintype "passive"))
    )
    (net (code "19") (name "/row5") (class "Default")
      (node (ref "D257") (pin "2") (pinfunction "K_2") (pintype "passive"))
      (node (ref "D258") (pin "2") (pinfunction "K_2") (pintype "passive"))
      (node (ref "D259") (pin "2") (pinfunction "K_2") (pintype "passive"))
      (node (ref "D260") (pin "2") (pinfunction "K_2") (pintype "passive"))
      (node (ref "D261") (pin "2") (pinfunction "K_2") (pintype "passive"))
      (node (ref "D262") (pin "2") (pinfunction "K_2") (pintype "passive"))
      (node (ref "D263") (pin "2") (pinfunction "K_2") (pintype "passive"))
      (node (ref "D264") (pin "2") (pinfunction "K_2") (pintype "passive"))
      (node (ref "D265") (pin "2") (pinfunction "K_2") (pintype "passive"))
      (node (ref "D266") (pin "2") (pinfunction "K_2") (pintype "passive"))
    )
    (net (code "20") (name "Net-(D201-A)") (class "Default")
      (node (ref "D201") (pin "1") (pinfunction "A_1") (pintype "passive"))
      (node (ref "S201") (pin "1") (pinfunction "1_1") (pintype "passive"))
    )
    (net (code "21") (name "Net-(D202-A)") (class "Default")
      (node (ref "D202") (pin "1") (pinfunction "A_1") (pintype "passive"))
      (node (ref "S202") (pin "1") (pinfunction "1_1") (pintype "passive"))
    )
    (net (code "22") (name "Net-(D203-A)") (class "Default")
      (node (ref "D203") (pin "1") (pinfunction "A_1") (pintype "passive"))
      (node (ref "S203") (pin "1") (pinfunction "1_1") (pintype "passive"))
    )
    (net (code "23") (name "Net-(D204-A)") (class "Default")
      (node (ref "D204") (pin "1") (pinfunction "A_1") (pintype "passive"))
      (node (ref "S204") (pin "1") (pinfunction "1_1") (pintype "passive"))
    )
    (net (code "24") (name "Net-(D205-A)") (class "Default")
      (node (ref "D205") (pin "1") (pinfunction "A_1") (pintype "passive"))
      (node (ref "S205") (pin "1") (pinfunction "1_1") (pintype "passive"))
    )
    (net (code "25") (name "Net-(D206-A)") (class "Default")
      (node (ref "D206") (pin "1") (pinfunction "A_1") (pintype "passive"))
      (node (ref "S206") (pin "1") (pinfunction "1_1") (pintype "passive"))
    )
    (net (code "26") (name "Net-(D207-A)") (class "Default")
      (node (ref "D207") (pin "1") (pinfunction "A_1") (pintype "passive"))
      (node (ref "S207") (pin "1") (pinfunction "1_1") (pintype "passive"))
    )
    (net (code "27") (name "Net-(D208-A)") (class "Default")
      (node (ref "D208") (pin "1") (pinfunction "A_1") (pintype "passive"))
      (node (ref "S208") (pin "1") (pinfunction "1_1") (pintype "passive"))
    )
    (net (code "28") (name "Net-(D209-A)") (class "Default")
      (node (ref "D209") (pin "1") (pinfunction "A_1") (pintype "passive"))
      (node (ref "S209") (pin "1") (pinfunction "1_1") (pintype "passive"))
    )
    (net (code "29") (name "Net-(D210-A)") (class "Default")
      (node (ref "D210") (pin "1") (pinfunction "A_1") (pintype "passive"))
      (node (ref "S210") (pin "1") (pinfunction "1_1") (pintype "passive"))
    )
    (net (code "30") (name "Net-(D211-A)") (class "Default")
      (node (ref "D211") (pin "1") (pinfunction "A_1") (pintype "passive"))
      (node (ref "S211") (pin "1") (pinfunction "1_1") (pintype "passive"))
    )
    (net (code "31") (name "Net-(D212-A)") (class "Default")
      (node (ref "D212") (pin "1") (pinfunction "A_1") (pintype "passive"))
      (node (ref "S212") (pin "1") (pinfunction "1_1") (pintype "passive"))
    )
    (net (code "32") (name "Net-(D213-A)") (class "Default")
      (node (ref "D213") (pin "1") (pinfunction "A_1") (pintype "passive"))
      (node (ref "S213") (pin "1") (pinfunction "1_1") (pintype "passive"))
    )
    (net (code "33") (name "Net-(D214-A)") (class "Default")
      (node (ref "D214") (pin "1") (pinfunction "A_1") (pintype "passive"))
      (node (ref "S214") (pin "1") (pinfunction "1_1") (pintype "passive"))
    )
    (net (code "34") (name "Net-(D215-A)") (class "Default")
      (node (ref "D215") (pin "1") (pinfunction "A_1") (pintype "passive"))
      (node (ref "S215") (pin "1") (pinfunction "1_1") (pintype "passive"))
    )
    (net (code "35") (name "Net-(D216-A)") (class "Default")
      (node (ref "D216") (pin "1") (pinfunction "A_1") (pintype "passive"))
      (node (ref "S216") (pin "1") (pinfunction "1_1") (pintype "passive"))
    )
    (net (code "36") (name "Net-(D217-A)") (class "Default")
      (node (ref "D217") (pin "1") (pinfunction "A_1") (pintype "passive"))
      (node (ref "S217") (pin "1") (pinfunction "1_1") (pintype "passive"))
    )
    (net (code "37") (name "Net-(D218-A)") (class "Default")
      (node (ref "D218") (pin "1") (pinfunction "A_1") (pintype "passive"))
      (node (ref "S218") (pin "1") (pinfunction "1_1") (pintype "passive"))
    )
    (net (code "38") (name "Net-(D219-A)") (class "Default")
      (node (ref "D219") (pin "1") (pinfunction "A_1") (pintype "passive"))
      (node (ref "S219") (pin "1") (pinfunction "1_1") (pintype "passive"))
    )
    (net (code "39") (name "Net-(D220-A)") (class "Default")
      (node (ref "D220") (pin "1") (pinfunction "A_1") (pintype "passive"))
      (node (ref "S220") (pin "1") (pinfunction "1_1") (pintype "passive"))
    )
    (net (code "40") (name "Net-(D221-A)") (class "Default")
      (node (ref "D221") (pin "1") (pinfunction "A_1") (pintype "passive"))
      (node (ref "S221") (pin "1") (pinfunction "1_1") (pintype "passive"))
    )
    (net (code "41") (name "Net-(D222-A)") (class "Default")
      (node (ref "D222") (pin "1") (pinfunction "A_1") (pintype "passive"))
      (node (ref "S222") (pin "1") (pinfunction "1_1") (pintype "passive"))
    )
    (net (code "42") (name "Net-(D223-A)") (class "Default")
      (node (ref "D223") (pin "1") (pinfunction "A_1") (pintype "passive"))
      (node (ref "S223") (pin "1") (pinfunction "1_1") (pintype "passive"))
    )
    (net (code "43") (name "Net-(D224-A)") (class "Default")
      (node (ref "D224") (pin "1") (pinfunction "A_1") (pintype "passive"))
      (node (ref "S224") (pin "1") (pinfunction "1_1") (pintype "passive"))
    )
    (net (code "44") (name "Net-(D225-A)") (class "Default")
      (node (ref "D225") (pin "1") (pinfunction "A_1") (pintype "passive"))
      (node (ref "S225") (pin "1") (pinfunction "1_1") (pintype "passive"))
    )
    (net (code "45") (name "Net-(D226-A)") (class "Default")
      (node (ref "D226") (pin "1") (pinfunction "A_1") (pintype "passive"))
      (node (ref "S226") (pin "1") (pinfunction "1_1") (pintype "passive"))
    )
    (net (code "46") (name "Net-(D227-A)") (class "Default")
      (node (ref "D227") (pin "1") (pinfunction "A_1") (pintype "passive"))
      (node (ref "S227") (pin "1") (pinfunction "1_1") (pintype "passive"))
    )
    (net (code "47") (name "Net-(D228-A)") (class "Default")
      (node (ref "D228") (pin "1") (pinfunction "A_1") (pintype "passive"))
      (node (ref "S259") (pin "1") (pinfunction "1_1") (pintype "passive"))
    )
    (net (code "48") (name "Net-(D229-A)") (class "Default")
      (node (ref "D229") (pin "1") (pinfunction "A_1") (pintype "passive"))
      (node (ref "S229") (pin "1") (pinfunction "1_1") (pintype "passive"))
    )
    (net (code "49") (name "Net-(D230-A)") (class "Default")
      (node (ref "D230") (pin "1") (pinfunction "A_1") (pintype "passive"))
      (node (ref "S230") (pin "1") (pinfunction "1_1") (pintype "passive"))
    )
    (net (code "50") (name "Net-(D231-A)") (class "Default")
      (node (ref "D231") (pin "1") (pinfunction "A_1") (pintype "passive"))
      (node (ref "S231") (pin "1") (pinfunction "1_1") (pintype "passive"))
    )
    (net (code "51") (name "Net-(D232-A)") (class "Default")
      (node (ref "D232") (pin "1") (pinfunction "A_1") (pintype "passive"))
      (node (ref "S232") (pin "1") (pinfunction "1_1") (pintype "passive"))
    )
    (net (code "52") (name "Net-(D233-A)") (class "Default")
      (node (ref "D233") (pin "1") (pinfunction "A_1") (pintype "passive"))
      (node (ref "S233") (pin "1") (pinfunction "1_1") (pintype "passive"))
    )
    (net (code "53") (name "Net-(D234-A)") (class "Default")
      (node (ref "D234") (pin "1") (pinfunction "A_1") (pintype "passive"))
      (node (ref "S234") (pin "1") (pinfunction "1_1") (pintype "passive"))
    )
    (net (code "54") (name "Net-(D235-A)") (class "Default")
      (node (ref "D235") (pin "1") (pinfunction "A_1") (pintype "passive"))
      (node (ref "S235") (pin "1") (pinfunction "1_1") (pintype "passive"))
    )
    (net (code "55") (name "Net-(D236-A)") (class "Default")
      (node (ref "D236") (pin "1") (pinfunction "A_1") (pintype "passive"))
      (node (ref "S236") (pin "1") (pinfunction "1_1") (pintype "passive"))
    )
    (net (code "56") (name "Net-(D237-A)") (class "Default")
      (node (ref "D237") (pin "1") (pinfunction "A_1") (pintype "passive"))
      (node (ref "S237") (pin "1") (pinfunction "1_1") (pintype "passive"))
    )
    (net (code "57") (name "Net-(D238-A)") (class "Default")
      (node (ref "D238") (pin "1") (pinfunction "A_1") (pintype "passive"))
      (node (ref "S238") (pin "1") (pinfunction "1_1") (pintype "passive"))
    )
    (net (code "58") (name "Net-(D239-A)") (class "Default")
      (node (ref "D239") (pin "1") (pinfunction "A_1") (pintype "passive"))
      (node (ref "S239") (pin "1") (pinfunction "1_1") (pintype "passive"))
    )
    (net (code "59") (name "Net-(D240-A)") (class "Default")
      (node (ref "D240") (pin "1") (pinfunction "A_1") (pintype "passive"))
      (node (ref "S240") (pin "1") (pinfunction "1_1") (pintype "passive"))
    )
    (net (code "60") (name "Net-(D241-A)") (class "Default")
      (node (ref "D241") (pin "1") (pinfunction "A_1") (pintype "passive"))
      (node (ref "S242") (pin "1") (pinfunction "1_1") (pintype "passive"))
    )
    (net (code "61") (name "Net-(D242-A)") (class "Default")
      (node (ref "D242") (pin "1") (pinfunction "A_1") (pintype "passive"))
      (node (ref "S228") (pin "1") (pinfunction "1_1") (pintype "passive"))
      (node (ref "S228_2") (pin "1") (pinfunction "1_1") (pintype "passive"))
    )
    (net (code "62") (name "Net-(D243-A)") (class "Default")
      (node (ref "D243") (pin "1") (pinfunction "A_1") (pintype "passive"))
      (node (ref "S243") (pin "1") (pinfunction "1_1") (pintype "passive"))
    )
    (net (code "63") (name "Net-(D244-A)") (class "Default")
      (node (ref "D244") (pin "1") (pinfunction "A_1") (pintype "passive"))
      (node (ref "S244") (pin "2") (pinfunction "2_2") (pintype "passive"))
    )
    (net (code "64") (name "Net-(D245-A)") (class "Default")
      (node (ref "D245") (pin "1") (pinfunction "A_1") (pintype "passive"))
      (node (ref "S245") (pin "1") (pinfunction "1_1") (pintype "passive"))
    )
    (net (code "65") (name "Net-(D246-A)") (class "Default")
      (node (ref "D246") (pin "1") (pinfunction "A_1") (pintype "passive"))
      (node (ref "S246") (pin "1") (pinfunction "1_1") (pintype "passive"))
    )
    (net (code "66") (name "Net-(D247-A)") (class "Default")
      (node (ref "D247") (pin "1") (pinfunction "A_1") (pintype "passive"))
      (node (ref "S247") (pin "1") (pinfunction "1_1") (pintype "passive"))
    )
    (net (code "67") (name "Net-(D248-A)") (class "Default")
      (node (ref "D248") (pin "1") (pinfunction "A_1") (pintype "passive"))
      (node (ref "S248") (pin "1") (pinfunction "1_1") (pintype "passive"))
    )
    (net (code "68") (name "Net-(D249-A)") (class "Default")
      (node (ref "D249") (pin "1") (pinfunction "A_1") (pintype "passive"))
      (node (ref "S249") (pin "1") (pinfunction "1_1") (pintype "passive"))
    )
    (net (code "69") (name "Net-(D250-A)") (class "Default")
      (node (ref "D250") (pin "1") (pinfunction "A_1") (pintype "passive"))
      (node (ref "S250") (pin "1") (pinfunction "1_1") (pintype "passive"))
    )
    (net (code "70") (name "Net-(D251-A)") (class "Default")
      (node (ref "D251") (pin "1") (pinfunction "A_1") (pintype "passive"))
      (node (ref "S251") (pin "1") (pinfunction "1_1") (pintype "passive"))
    )
    (net (code "71") (name "Net-(D252-A)") (class "Default")
      (node (ref "D252") (pin "1") (pinfunction "A_1") (pintype "passive"))
      (node (ref "S252") (pin "1") (pinfunction "1_1") (pintype "passive"))
    )
    (net (code "72") (name "Net-(D253-A)") (class "Default")
      (node (ref "D253") (pin "1") (pinfunction "A_1") (pintype "passive"))
      (node (ref "S253") (pin "1") (pinfunction "1_1") (pintype "passive"))
    )
    (net (code "73") (name "Net-(D254-A)") (class "Default")
      (node (ref "D254") (pin "1") (pinfunction "A_1") (pintype "passive"))
      (node (ref "S254") (pin "1") (pinfunction "1_1") (pintype "passive"))
    )
    (net (code "74") (name "Net-(D255-A)") (class "Default")
      (node (ref "D255") (pin "1") (pinfunction "A_1") (pintype "passive"))
      (node (ref "S256") (pin "1") (pinfunction "1_1") (pintype "passive"))
    )
    (net (code "75") (name "Net-(D256-A)") (class "Default")
      (node (ref "D256") (pin "1") (pinfunction "A_1") (pintype "passive"))
      (node (ref "S269") (pin "1") (pinfunction "1_1") (pintype "passive"))
    )
    (net (code "76") (name "Net-(D257-A)") (class "Default")
      (node (ref "D257") (pin "1") (pinfunction "A_1") (pintype "passive"))
      (node (ref "S257") (pin "2") (pinfunction "2_2") (pintype "passive"))
    )
    (net (code "77") (name "Net-(D258-A)") (class "Default")
      (node (ref "D258") (pin "1") (pinfunction "A_1") (pintype "passive"))
      (node (ref "S258") (pin "2") (pinfunction "2_2") (pintype "passive"))
    )
    (net (code "78") (name "Net-(D259-A)") (class "Default")
      (node (ref "D259") (pin "1") (pinfunction "A_1") (pintype "passive"))
      (node (ref "S260") (pin "2") (pinfunction "2_2") (pintype "passive"))
    )
    (net (code "79") (name "Net-(D260-A)") (class "Default")
      (node (ref "D260") (pin "1") (pinfunction "A_1") (pintype "passive"))
      (node (ref "S261") (pin "1") (pinfunction "1_1") (pintype "passive"))
    )
    (net (code "80") (name "Net-(D261-A)") (class "Default")
      (node (ref "D261") (pin "1") (pinfunction "A_1") (pintype "passive"))
      (node (ref "S262") (pin "2") (pinfunction "2_2") (pintype "passive"))
    )
    (net (code "81") (name "Net-(D262-A)") (class "Default")
      (node (ref "D262") (pin "1") (pinfunction "A_1") (pintype "passive"))
      (node (ref "S263") (pin "2") (pinfunction "2_2") (pintype "passive"))
    )
    (net (code "82") (name "Net-(D263-A)") (class "Default")
      (node (ref "D263") (pin "1") (pinfunction "A_1") (pintype "passive"))
      (node (ref "S264") (pin "1") (pinfunction "1_1") (pintype "passive"))
    )
    (net (code "83") (name "Net-(D264-A)") (class "Default")
      (node (ref "D264") (pin "1") (pinfunction "A_1") (pintype "passive"))
      (node (ref "S265") (pin "1") (pinfunction "1_1") (pintype "passive"))
    )
    (net (code "84") (name "Net-(D265-A)") (class "Default")
      (node (ref "D265") (pin "1") (pinfunction "A_1") (pintype "passive"))
      (node (ref "S241") (pin "1") (pinfunction "1_1") (pintype "passive"))
    )
    (net (code "85") (name "Net-(D266-A)") (class "Default")
      (node (ref "D266") (pin "1") (pinfunction "A_1") (pintype "passive"))
      (node (ref "S266") (pin "1") (pinfunction "1_1") (pintype "passive"))
    )
  )
)
